# USB-Debug.net
KiCad netlist of a schematic drawn in Altium Designer
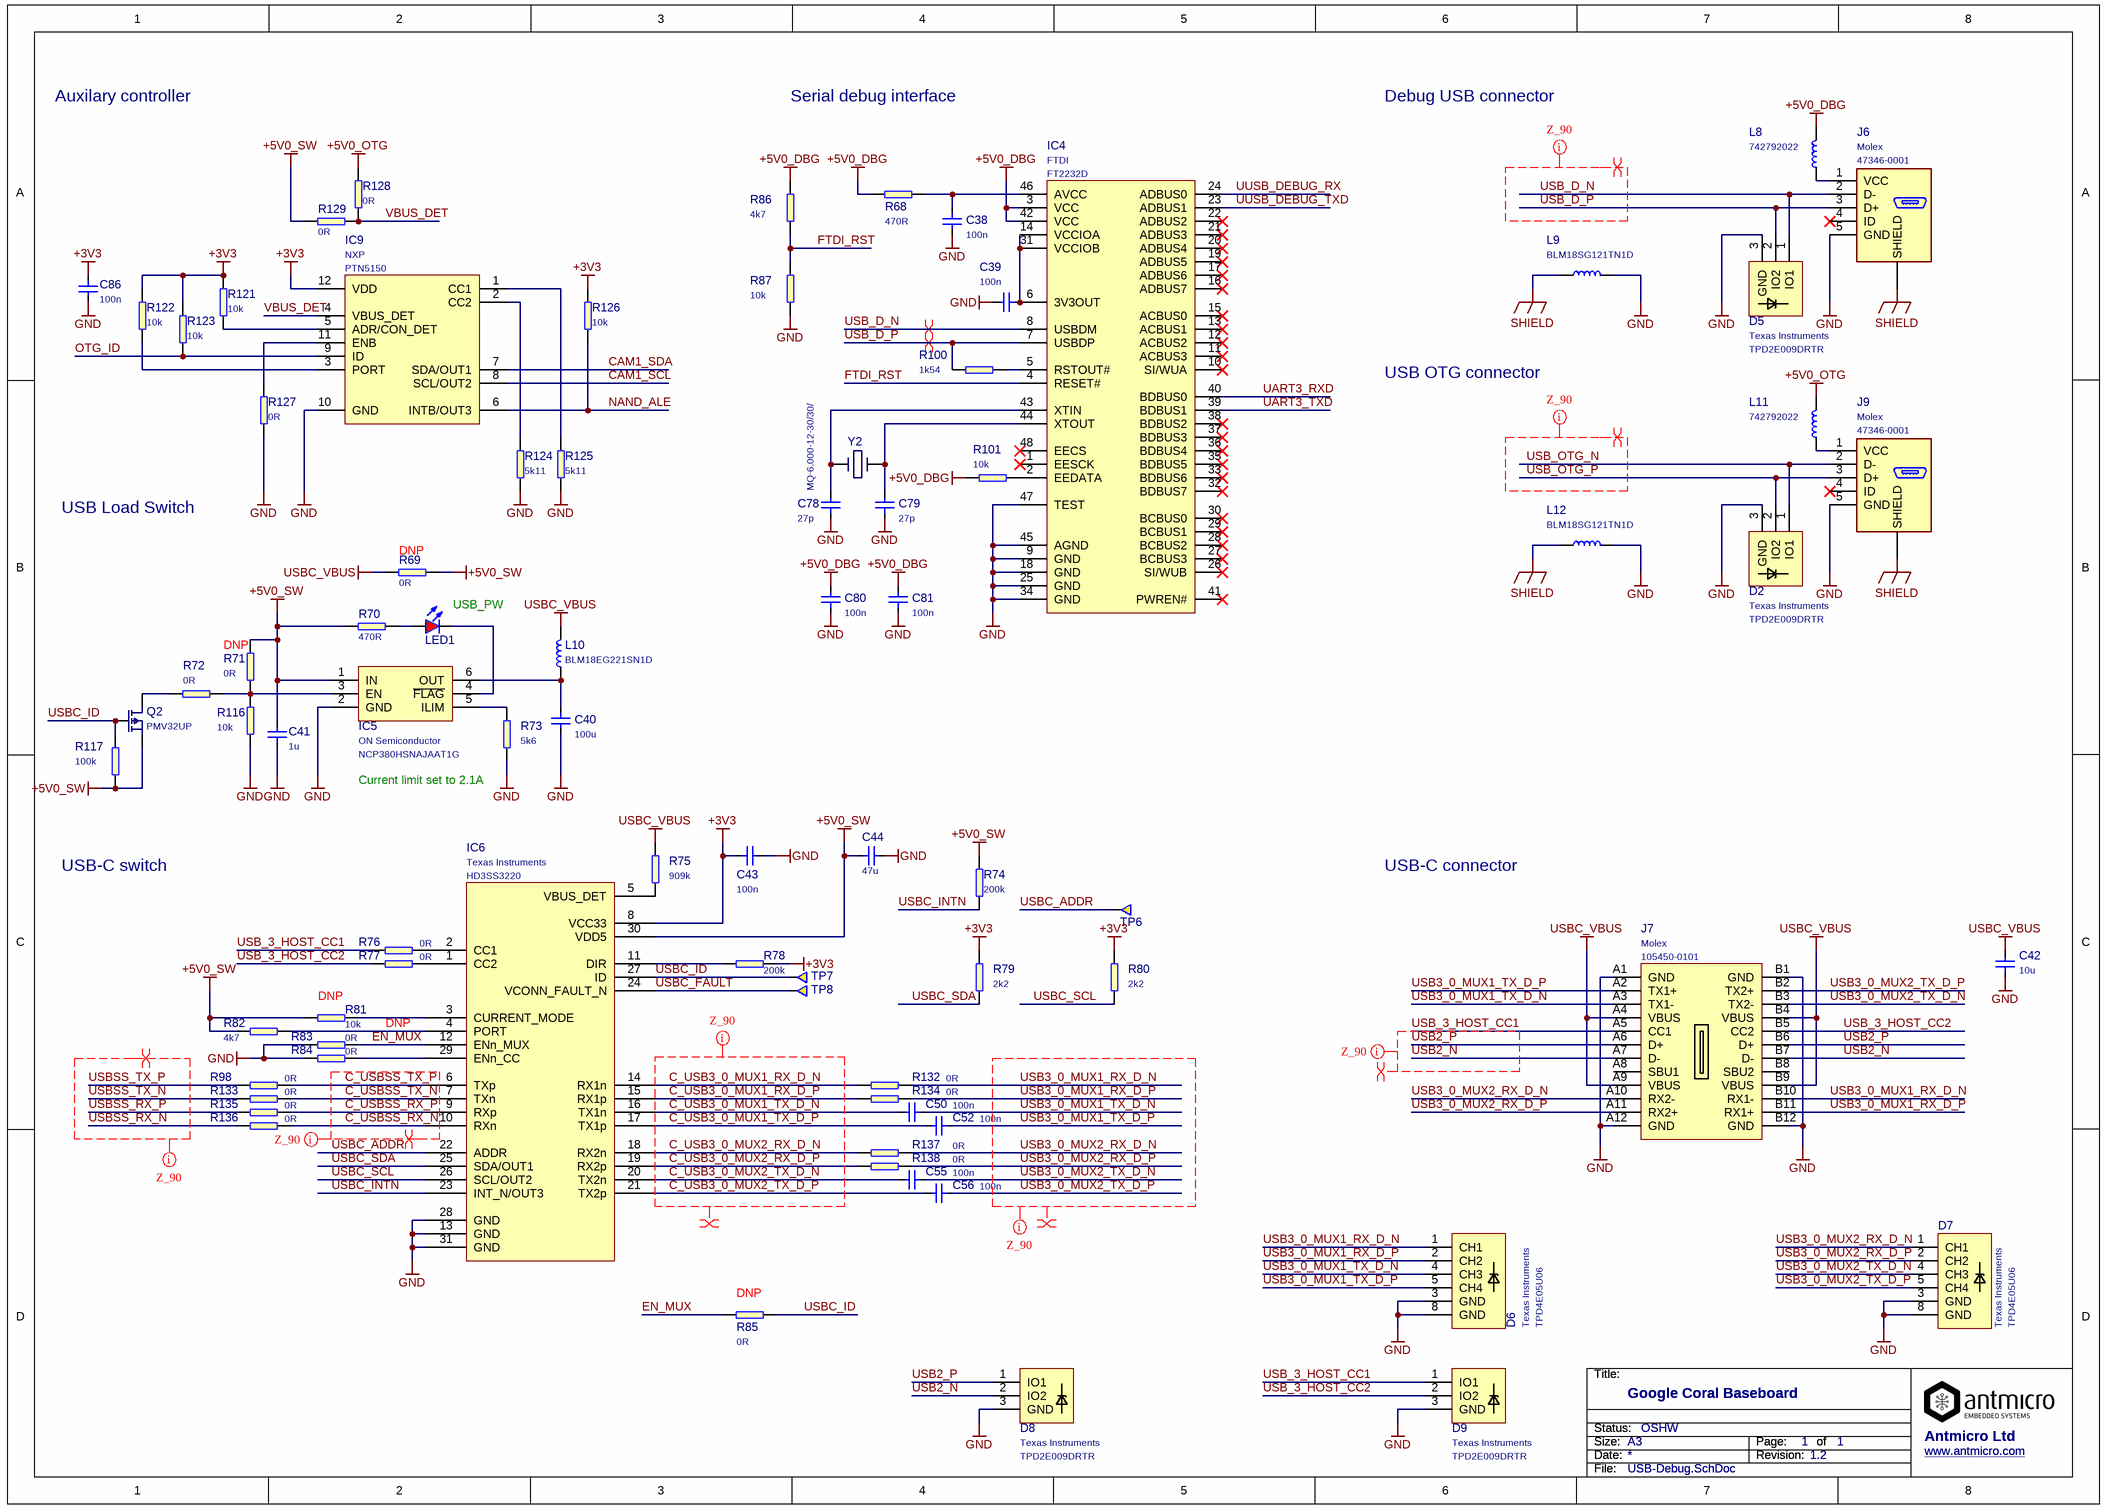
[diagram p0: USB-Debug.SchDoc]

(export (version "E")
  (design (tool "Eeschema 10.0.6"))
  (components
    (comp (ref "C38")
      (value "100n")
      (footprint "C_0402")
      (description "MLCC SMT Capacitor 100nF 0402")
      (fields (field (name "PARTNUMBER") "C_100n_0402"))
      (libsource (lib "altium-import") (part "root_3_C_"))
    )
    (comp (ref "C39")
      (value "100n")
      (footprint "C_0402")
      (description "MLCC SMT Capacitor 100nF 0402")
      (fields (field (name "PARTNUMBER") "C_100n_0402"))
      (libsource (lib "altium-import") (part "root_2_C_"))
    )
    (comp (ref "C40")
      (value "100u")
      (footprint "1210")
      (description "MLCC SMT Capacitor 100uF 1210 X5R")
      (fields (field (name "PARTNUMBER") "C_100u_1210_X5R"))
      (libsource (lib "altium-import") (part "root_3_C_"))
    )
    (comp (ref "C41")
      (value "1u")
      (footprint "0603")
      (description "MLCC SMT Capacitor 1uF 0603")
      (fields (field (name "PARTNUMBER") "C_1u_0603"))
      (libsource (lib "altium-import") (part "root_1_C_"))
    )
    (comp (ref "C42")
      (value "10u")
      (footprint "0603")
      (description "MLCC SMT Capacitor 10uF 0603")
      (fields (field (name "PARTNUMBER") "C_10u_0603"))
      (libsource (lib "altium-import") (part "root_1_C_"))
    )
    (comp (ref "C43")
      (value "100n")
      (footprint "0603")
      (description "MLCC SMT Capacitor 100nF 0603")
      (fields (field (name "PARTNUMBER") "C_100n_0603") (field (name "MANUFACTURER") "AVX"))
      (libsource (lib "altium-import") (part "root_0_C_"))
    )
    (comp (ref "C44")
      (value "47u")
      (footprint "0805")
      (description "MLCC SMT Capacitor 47uF 0805")
      (fields (field (name "PARTNUMBER") "C_47u_0805") (field (name "MANUFACTURER") "KEMET"))
      (libsource (lib "altium-import") (part "root_0_C_"))
    )
    (comp (ref "C50")
      (value "100n")
      (footprint "C_0402")
      (description "MLCC SMT Capacitor 100nF 0402")
      (fields (field (name "PARTNUMBER") "C_100n_0402"))
      (libsource (lib "altium-import") (part "root_2_C_"))
    )
    (comp (ref "C52")
      (value "100n")
      (footprint "C_0402")
      (description "MLCC SMT Capacitor 100nF 0402")
      (fields (field (name "PARTNUMBER") "C_100n_0402"))
      (libsource (lib "altium-import") (part "root_2_C_"))
    )
    (comp (ref "C55")
      (value "100n")
      (footprint "C_0402")
      (description "MLCC SMT Capacitor 100nF 0402")
      (fields (field (name "PARTNUMBER") "C_100n_0402"))
      (libsource (lib "altium-import") (part "root_2_C_"))
    )
    (comp (ref "C56")
      (value "100n")
      (footprint "C_0402")
      (description "MLCC SMT Capacitor 100nF 0402")
      (fields (field (name "PARTNUMBER") "C_100n_0402"))
      (libsource (lib "altium-import") (part "root_2_C_"))
    )
    (comp (ref "C78")
      (value "27p")
      (footprint "C_0402")
      (description "MLCC SMT Capacitor 27pF 0402")
      (fields (field (name "PARTNUMBER") "C_27p_0402"))
      (libsource (lib "altium-import") (part "root_1_C_"))
    )
    (comp (ref "C79")
      (value "27p")
      (footprint "C_0402")
      (description "MLCC SMT Capacitor 27pF 0402")
      (fields (field (name "PARTNUMBER") "C_27p_0402"))
      (libsource (lib "altium-import") (part "root_1_C_"))
    )
    (comp (ref "C80")
      (value "100n")
      (footprint "C_0402")
      (description "MLCC SMT Capacitor 100nF 0402")
      (fields (field (name "PARTNUMBER") "C_100n_0402"))
      (libsource (lib "altium-import") (part "root_1_C_"))
    )
    (comp (ref "C81")
      (value "100n")
      (footprint "C_0402")
      (description "MLCC SMT Capacitor 100nF 0402")
      (fields (field (name "PARTNUMBER") "C_100n_0402"))
      (libsource (lib "altium-import") (part "root_1_C_"))
    )
    (comp (ref "C86")
      (value "100n")
      (footprint "C_0402")
      (description "MLCC SMT Capacitor 100nF 0402")
      (fields (field (name "PARTNUMBER") "C_100n_0402"))
      (libsource (lib "altium-import") (part "root_3_C_"))
    )
    (comp (ref "D2")
      (value "TPD2E009DRTR")
      (footprint "SOT-3")
      (description "ESD Suppressors 2-CH")
      (fields (field (name "MANUFACTURER") "Texas Instruments"))
      (libsource (lib "altium-import") (part "root_3_TPD2E009_"))
    )
    (comp (ref "D5")
      (value "TPD2E009DRTR")
      (footprint "SOT-3")
      (description "ESD Suppressors 2-CH")
      (fields (field (name "MANUFACTURER") "Texas Instruments"))
      (libsource (lib "altium-import") (part "root_3_TPD2E009_"))
    )
    (comp (ref "D6")
      (value "TPD4E05U06")
      (footprint "TPD4E05U06_PASS")
      (description "ESD Suppressors 4-CH")
      (fields (field (name "PARTNUMBER") "TPD4E05U06") (field (name "MANUFACTURER") "Texas Instruments"))
      (libsource (lib "altium-import") (part "root_0_TPD4E05U06_"))
    )
    (comp (ref "D7")
      (value "TPD4E05U06")
      (footprint "TPD4E05U06_PASS")
      (description "ESD Suppressors 4-CH")
      (fields (field (name "PARTNUMBER") "TPD4E05U06") (field (name "MANUFACTURER") "Texas Instruments"))
      (libsource (lib "altium-import") (part "root_0_TPD4E05U06_"))
    )
    (comp (ref "D8")
      (value "TPD2E009DRTR")
      (footprint "SOT-3")
      (description "ESD Suppressors 2-CH")
      (fields (field (name "MANUFACTURER") "Texas Instruments"))
      (libsource (lib "altium-import") (part "root_0_TPD2E009_"))
    )
    (comp (ref "D9")
      (value "TPD2E009DRTR")
      (footprint "SOT-3")
      (description "ESD Suppressors 2-CH")
      (fields (field (name "MANUFACTURER") "Texas Instruments"))
      (libsource (lib "altium-import") (part "root_0_TPD2E009_"))
    )
    (comp (ref "IC4")
      (value "FT2232D")
      (footprint "LQFP-48")
      (description "Dual USB-UART/FIFO")
      (fields (field (name "MANUFACTURER") "FTDI"))
      (libsource (lib "altium-import") (part "root_0_FT2232_"))
    )
    (comp (ref "IC5")
      (value "NCP380HSNAJAAT1G")
      (footprint "TSOP-6")
      (description "POWER LOAD SWITCH, HIGH SIDE")
      (fields (field (name "MANUFACTURER") "ON Semiconductor"))
      (libsource (lib "altium-import") (part "root_0_NCP380HSNAJAAT1G_"))
    )
    (comp (ref "IC6")
      (value "HD3SS3220")
      (footprint "RNH0030A")
      (description "IC DRP PORT CTLR USB-C 30WQFN")
      (fields (field (name "MANUFACTURER") "Texas Instruments"))
      (libsource (lib "altium-import") (part "root_0_HD3SS3220_"))
    )
    (comp (ref "IC9")
      (value "PTN5150")
      (footprint "PTN5150")
      (description "CC logic for USB Type-C applications")
      (fields (field (name "MANUFACTURER") "NXP"))
      (libsource (lib "altium-import") (part "root_0_PTN5150_"))
    )
    (comp (ref "J6")
      (value "47346-0001")
      (footprint "CON-Molex-047346-0001")
      (description "USB - micro B Receptacle Connector 5 Position Surface Mount, Right Angle, Horizontal")
      (fields (field (name "MANUFACTURER") "Molex"))
      (libsource (lib "altium-import") (part "root_0_Micro USB B_"))
    )
    (comp (ref "J7")
      (value "105450-0101")
      (footprint "CON-Molex-105450-0101")
      (description "USB-C connector")
      (fields (field (name "PARTNUMBER") "CON-Molex-105450-0101") (field (name "MANUFACTURER") "Molex"))
      (libsource (lib "altium-import") (part "root_0_CON-Molex-105450-0101_"))
    )
    (comp (ref "J9")
      (value "47346-0001")
      (footprint "CON-Molex-047346-0001")
      (description "USB - micro B Receptacle Connector 5 Position Surface Mount, Right Angle, Horizontal")
      (fields (field (name "PARTNUMBER") "47346-0001") (field (name "MANUFACTURER") "Molex"))
      (libsource (lib "altium-import") (part "root_0_Micro USB B_"))
    )
    (comp (ref "L8")
      (value "742792022")
      (footprint "0805")
      (description "WURTH ELEKTRONIK - 742792022 - FERRITE BEAD, 0.05OHM, 2A, 0805")
      (fields (field (name "MANUFACTURER") "WURTH ELEKTRONIK"))
      (libsource (lib "altium-import") (part "root_1_Inductor SMT_"))
    )
    (comp (ref "L9")
      (value "BLM18SG121TN1D")
      (footprint "0603")
      (description "FERRITE BEAD, 0.025OHM, 3A, 0603")
      (fields (field (name "MANUFACTURER") "MURATA") (field (name "PARTNUMBER") "BLM18EG221SN1D"))
      (libsource (lib "altium-import") (part "root_0_Inductor SMT_"))
    )
    (comp (ref "L10")
      (value "BLM18EG221SN1D")
      (footprint "0603")
      (description "MURATA 	BLM18EG221SN1D  FERRITE BEAD, 0.05OHM, 2A, 0603")
      (fields (field (name "MANUFACTURER") "MURATA"))
      (libsource (lib "altium-import") (part "root_1_Inductor SMT_"))
    )
    (comp (ref "L11")
      (value "742792022")
      (footprint "0805")
      (description "WURTH ELEKTRONIK - 742792022 - FERRITE BEAD, 0.05OHM, 2A, 0805")
      (fields (field (name "MANUFACTURER") "WURTH ELEKTRONIK"))
      (libsource (lib "altium-import") (part "root_1_Inductor SMT_"))
    )
    (comp (ref "L12")
      (value "BLM18SG121TN1D")
      (footprint "0603")
      (description "FERRITE BEAD, 0.025OHM, 3A, 0603")
      (fields (field (name "MANUFACTURER") "MURATA"))
      (libsource (lib "altium-import") (part "root_0_Inductor SMT_"))
    )
    (comp (ref "LED1")
      (value "KPT-1608EC")
      (footprint "LED0603")
      (description "LED Red 0603 case")
      (fields (field (name "MANUFACTURER") "KINGBRIGHT"))
      (libsource (lib "altium-import") (part "root_0_LED_"))
    )
    (comp (ref "Q2")
      (value "PMV32UP")
      (footprint "SOT-23")
      (description "P CH, 20V, 4A")
      (fields (field (name "MANUFACTURER") "NXP"))
      (libsource (lib "altium-import") (part "root_2_mirrored_PMOS_"))
    )
    (comp (ref "R68")
      (value "470R")
      (footprint "0402")
      (description "SMT Resistor 470R 0402")
      (fields (field (name "PARTNUMBER") "R_470R_0402"))
      (libsource (lib "altium-import") (part "root_0_R_"))
    )
    (comp (ref "R69")
      (value "0R")
      (footprint "0603")
      (description "SMT Resistor 0R 0603")
      (fields (field (name "PARTNUMBER") "R_0R_0603"))
      (libsource (lib "altium-import") (part "root_0_R_"))
    )
    (comp (ref "R70")
      (value "470R")
      (footprint "0603")
      (description "SMT Resistor 470R 0603")
      (fields (field (name "PARTNUMBER") "R_470R_0603"))
      (libsource (lib "altium-import") (part "root_2_R_"))
    )
    (comp (ref "R71")
      (value "0R")
      (footprint "0402")
      (description "SMT Resistor 0402")
      (fields (field (name "PARTNUMBER") "R_0R_0402"))
      (libsource (lib "altium-import") (part "root_1_R_"))
    )
    (comp (ref "R72")
      (value "0R")
      (footprint "0402")
      (description "SMT Resistor 0402")
      (fields (field (name "PARTNUMBER") "R_0R_0402"))
      (libsource (lib "altium-import") (part "root_0_R_"))
    )
    (comp (ref "R73")
      (value "5k6")
      (footprint "0603")
      (description "SMT Resistor 5k6 0603")
      (fields (field (name "PARTNUMBER") "R_5k6_0603"))
      (libsource (lib "altium-import") (part "root_1_R_"))
    )
    (comp (ref "R74")
      (value "200k")
      (footprint "0402")
      (description "SMT Resistor 200k 0402")
      (fields (field (name "PARTNUMBER") "R_200k_0402"))
      (libsource (lib "altium-import") (part "root_1_R_"))
    )
    (comp (ref "R75")
      (value "909k")
      (footprint "0402")
      (description "SMT Resistor 9k31 0402")
      (fields (field (name "PARTNUMBER") "R_909k_0402"))
      (libsource (lib "altium-import") (part "root_1_R_"))
    )
    (comp (ref "R76")
      (value "0R")
      (footprint "0402")
      (description "SMT Resistor 0402")
      (fields (field (name "PARTNUMBER") "R_0R_0402"))
      (libsource (lib "altium-import") (part "root_0_R_"))
    )
    (comp (ref "R77")
      (value "0R")
      (footprint "0402")
      (description "SMT Resistor 0402")
      (fields (field (name "PARTNUMBER") "R_0R_0402"))
      (libsource (lib "altium-import") (part "root_0_R_"))
    )
    (comp (ref "R78")
      (value "200k")
      (footprint "0402")
      (description "SMT Resistor 200k 0402")
      (fields (field (name "PARTNUMBER") "R_200k_0402"))
      (libsource (lib "altium-import") (part "root_0_R_"))
    )
    (comp (ref "R79")
      (value "2k2")
      (footprint "0402")
      (description "RES, 2k2, 0402, 5%")
      (fields (field (name "PARTNUMBER") "R_2k2_0402"))
      (libsource (lib "altium-import") (part "root_1_R_"))
    )
    (comp (ref "R80")
      (value "2k2")
      (footprint "0402")
      (description "RES, 2k2, 0402, 5%")
      (fields (field (name "PARTNUMBER") "R_2k2_0402"))
      (libsource (lib "altium-import") (part "root_1_R_"))
    )
    (comp (ref "R81")
      (value "10k")
      (footprint "0402")
      (description "SMT Resistor 0402")
      (fields (field (name "PARTNUMBER") "R_10k_0402"))
      (libsource (lib "altium-import") (part "root_0_R_"))
    )
    (comp (ref "R82")
      (value "4k7")
      (footprint "0402")
      (description "SMT Resistor 4k7 0402")
      (fields (field (name "PARTNUMBER") "R_4k7_0402"))
      (libsource (lib "altium-import") (part "root_0_R_"))
    )
    (comp (ref "R83")
      (value "0R")
      (footprint "0402")
      (description "SMT Resistor 0402")
      (fields (field (name "PARTNUMBER") "R_0R_0402"))
      (libsource (lib "altium-import") (part "root_0_R_"))
    )
    (comp (ref "R84")
      (value "0R")
      (footprint "0402")
      (description "SMT Resistor 0402")
      (fields (field (name "PARTNUMBER") "R_0R_0402"))
      (libsource (lib "altium-import") (part "root_0_R_"))
    )
    (comp (ref "R85")
      (value "0R")
      (footprint "0402")
      (description "SMT Resistor 0402")
      (fields (field (name "PARTNUMBER") "R_0R_0402"))
      (libsource (lib "altium-import") (part "root_0_R_"))
    )
    (comp (ref "R86")
      (value "4k7")
      (footprint "0402")
      (description "SMT Resistor 4k7 0402")
      (fields (field (name "PARTNUMBER") "R_4k7_0402"))
      (libsource (lib "altium-import") (part "root_1_R_"))
    )
    (comp (ref "R87")
      (value "10k")
      (footprint "0402")
      (description "SMT Resistor 0402")
      (fields (field (name "PARTNUMBER") "R_10k_0402"))
      (libsource (lib "altium-import") (part "root_1_R_"))
    )
    (comp (ref "R98")
      (value "0R")
      (footprint "0402")
      (description "SMT Resistor 0402")
      (fields (field (name "PARTNUMBER") "R_0R_0402"))
      (libsource (lib "altium-import") (part "root_0_R_"))
    )
    (comp (ref "R100")
      (value "1k54")
      (footprint "0402")
      (description "SMT Resistor 1k54 0402")
      (fields (field (name "PARTNUMBER") "R_1k54_0402"))
      (libsource (lib "altium-import") (part "root_0_R_"))
    )
    (comp (ref "R101")
      (value "10k")
      (footprint "0402")
      (description "SMT Resistor 0402")
      (fields (field (name "PARTNUMBER") "R_10k_0402"))
      (libsource (lib "altium-import") (part "root_0_R_"))
    )
    (comp (ref "R116")
      (value "10k")
      (footprint "0402")
      (description "SMT Resistor 0402")
      (fields (field (name "PARTNUMBER") "R_10k_0402"))
      (libsource (lib "altium-import") (part "root_1_R_"))
    )
    (comp (ref "R117")
      (value "100k")
      (footprint "0402")
      (description "SMT Resistor 100k 0402")
      (fields (field (name "PARTNUMBER") "R_100k_0402"))
      (libsource (lib "altium-import") (part "root_1_R_"))
    )
    (comp (ref "R121")
      (value "10k")
      (footprint "0402")
      (description "SMT Resistor 0402")
      (fields (field (name "PARTNUMBER") "R_10k_0402"))
      (libsource (lib "altium-import") (part "root_1_R_"))
    )
    (comp (ref "R122")
      (value "10k")
      (footprint "0402")
      (description "SMT Resistor 0402")
      (fields (field (name "PARTNUMBER") "R_10k_0402"))
      (libsource (lib "altium-import") (part "root_1_R_"))
    )
    (comp (ref "R123")
      (value "10k")
      (footprint "0402")
      (description "SMT Resistor 0402")
      (fields (field (name "PARTNUMBER") "R_10k_0402"))
      (libsource (lib "altium-import") (part "root_1_R_"))
    )
    (comp (ref "R124")
      (value "5k11")
      (footprint "0402")
      (description "SMT Resistor 5k11 0402")
      (fields (field (name "PARTNUMBER") "R_5k11_0402"))
      (libsource (lib "altium-import") (part "root_1_R_"))
    )
    (comp (ref "R125")
      (value "5k11")
      (footprint "0402")
      (description "SMT Resistor 5k11 0402")
      (fields (field (name "PARTNUMBER") "R_5k11_0402"))
      (libsource (lib "altium-import") (part "root_1_R_"))
    )
    (comp (ref "R126")
      (value "10k")
      (footprint "0402")
      (description "SMT Resistor 0402")
      (fields (field (name "PARTNUMBER") "R_10k_0402"))
      (libsource (lib "altium-import") (part "root_1_R_"))
    )
    (comp (ref "R127")
      (value "0R")
      (footprint "0402")
      (description "SMT Resistor 0402")
      (fields (field (name "PARTNUMBER") "R_0R_0402"))
      (libsource (lib "altium-import") (part "root_1_R_"))
    )
    (comp (ref "R128")
      (value "0R")
      (footprint "0402")
      (description "SMT Resistor 0402")
      (fields (field (name "PARTNUMBER") "R_0R_0402"))
      (libsource (lib "altium-import") (part "root_1_R_"))
    )
    (comp (ref "R129")
      (value "0R")
      (footprint "0402")
      (description "SMT Resistor 0402")
      (fields (field (name "PARTNUMBER") "R_0R_0402"))
      (libsource (lib "altium-import") (part "root_2_R_"))
    )
    (comp (ref "R132")
      (value "0R")
      (footprint "0402")
      (description "SMT Resistor 0402")
      (fields (field (name "PARTNUMBER") "R_0R_0402"))
      (libsource (lib "altium-import") (part "root_0_R_"))
    )
    (comp (ref "R133")
      (value "0R")
      (footprint "0402")
      (description "SMT Resistor 0402")
      (fields (field (name "PARTNUMBER") "R_0R_0402"))
      (libsource (lib "altium-import") (part "root_0_R_"))
    )
    (comp (ref "R134")
      (value "0R")
      (footprint "0402")
      (description "SMT Resistor 0402")
      (fields (field (name "PARTNUMBER") "R_0R_0402"))
      (libsource (lib "altium-import") (part "root_0_R_"))
    )
    (comp (ref "R135")
      (value "0R")
      (footprint "0402")
      (description "SMT Resistor 0402")
      (fields (field (name "PARTNUMBER") "R_0R_0402"))
      (libsource (lib "altium-import") (part "root_0_R_"))
    )
    (comp (ref "R136")
      (value "0R")
      (footprint "0402")
      (description "SMT Resistor 0402")
      (fields (field (name "PARTNUMBER") "R_0R_0402"))
      (libsource (lib "altium-import") (part "root_0_R_"))
    )
    (comp (ref "R137")
      (value "0R")
      (footprint "0402")
      (description "SMT Resistor 0402")
      (fields (field (name "PARTNUMBER") "R_0R_0402"))
      (libsource (lib "altium-import") (part "root_0_R_"))
    )
    (comp (ref "R138")
      (value "0R")
      (footprint "0402")
      (description "SMT Resistor 0402")
      (fields (field (name "PARTNUMBER") "R_0R_0402"))
      (libsource (lib "altium-import") (part "root_0_R_"))
    )
    (comp (ref "TP6")
      (value "Testpad")
      (footprint "TP-R-1.5")
      (description "Testpad, round, 1.5mm")
      (libsource (lib "altium-import") (part "root_3_Testpad_"))
    )
    (comp (ref "TP7")
      (value "Testpad")
      (footprint "TP-R-1.5")
      (description "Testpad, round, 1.5mm")
      (libsource (lib "altium-import") (part "root_3_Testpad_"))
    )
    (comp (ref "TP8")
      (value "Testpad")
      (footprint "TP-R-1.5")
      (description "Testpad, round, 1.5mm")
      (libsource (lib "altium-import") (part "root_3_Testpad_"))
    )
    (comp (ref "Y2")
      (value "MQ-6.000-12-30/30/")
      (footprint "Crystal_5x7mm")
      (description "CRYSTAL, 6MHZ, 12PF, SMD,30ppm")
      (fields
        (field (name "PARTNUMBER") "CRYSTAL_6_MHz_SMD")
        (field (name "MANUFACTURER") "MERCURY UNITED ELECTRONICS")
      )
      (libsource (lib "altium-import") (part "root_0_CRYSTAL_6Mhz_"))
    )
  )
  (nets
    (net (code "1") (name "+3V3") (class "Default")
      (node (ref "C43") (pin "1") (pinfunction "1_1") (pintype "passive"))
      (node (ref "C86") (pin "1") (pinfunction "1_1") (pintype "passive"))
      (node (ref "IC6") (pin "8") (pinfunction "VCC33_8") (pintype "passive"))
      (node (ref "IC9") (pin "12") (pinfunction "VDD_12") (pintype "passive"))
      (node (ref "R121") (pin "2") (pintype "passive"))
      (node (ref "R122") (pin "2") (pintype "passive"))
      (node (ref "R123") (pin "2") (pintype "passive"))
      (node (ref "R126") (pin "2") (pintype "passive"))
      (node (ref "R78") (pin "2") (pintype "passive"))
      (node (ref "R79") (pin "2") (pintype "passive"))
      (node (ref "R80") (pin "2") (pintype "passive"))
    )
    (net (code "2") (name "+5V0_DBG") (class "Default")
      (node (ref "C80") (pin "2") (pinfunction "2_2") (pintype "passive"))
      (node (ref "C81") (pin "2") (pinfunction "2_2") (pintype "passive"))
      (node (ref "IC4") (pin "3") (pinfunction "VCC_3") (pintype "passive"))
      (node (ref "IC4") (pin "42") (pinfunction "VCC_42") (pintype "passive"))
      (node (ref "L8") (pin "2") (pintype "passive"))
      (node (ref "R101") (pin "1") (pintype "passive"))
      (node (ref "R68") (pin "1") (pintype "passive"))
      (node (ref "R86") (pin "2") (pintype "passive"))
    )
    (net (code "3") (name "+5V0_OTG") (class "Default")
      (node (ref "L11") (pin "2") (pintype "passive"))
      (node (ref "R128") (pin "2") (pintype "passive"))
    )
    (net (code "4") (name "+5V0_SW") (class "Default")
      (node (ref "C41") (pin "2") (pinfunction "2_2") (pintype "passive"))
      (node (ref "C44") (pin "1") (pinfunction "1_1") (pintype "passive"))
      (node (ref "IC5") (pin "1") (pinfunction "IN_1") (pintype "passive"))
      (node (ref "IC6") (pin "30") (pinfunction "VDD5_30") (pintype "passive"))
      (node (ref "Q2") (pin "2") (pinfunction "S_2") (pintype "passive"))
      (node (ref "R117") (pin "1") (pintype "passive"))
      (node (ref "R129") (pin "2") (pintype "passive"))
      (node (ref "R69") (pin "2") (pintype "passive"))
      (node (ref "R70") (pin "2") (pintype "passive"))
      (node (ref "R71") (pin "2") (pintype "passive"))
      (node (ref "R74") (pin "2") (pintype "passive"))
      (node (ref "R81") (pin "1") (pintype "passive"))
      (node (ref "R82") (pin "1") (pintype "passive"))
    )
    (net (code "5") (name "/CAM1_SCL") (class "Default")
      (node (ref "IC9") (pin "8") (pinfunction "SCL/OUT2_8") (pintype "passive"))
    )
    (net (code "6") (name "/CAM1_SDA") (class "Default")
      (node (ref "IC9") (pin "7") (pinfunction "SDA/OUT1_7") (pintype "passive"))
    )
    (net (code "7") (name "/C_USB3_0_MUX1_RX_D_N") (class "Default")
      (node (ref "IC6") (pin "14") (pinfunction "RX1n_14") (pintype "passive"))
      (node (ref "R132") (pin "1") (pintype "passive"))
    )
    (net (code "8") (name "/C_USB3_0_MUX1_RX_D_P") (class "Default")
      (node (ref "IC6") (pin "15") (pinfunction "RX1p_15") (pintype "passive"))
      (node (ref "R134") (pin "1") (pintype "passive"))
    )
    (net (code "9") (name "/C_USB3_0_MUX1_TX_D_N") (class "Default")
      (node (ref "C50") (pin "2") (pinfunction "2_2") (pintype "passive"))
      (node (ref "IC6") (pin "16") (pinfunction "TX1n_16") (pintype "passive"))
    )
    (net (code "10") (name "/C_USB3_0_MUX1_TX_D_P") (class "Default")
      (node (ref "C52") (pin "2") (pinfunction "2_2") (pintype "passive"))
      (node (ref "IC6") (pin "17") (pinfunction "TX1p_17") (pintype "passive"))
    )
    (net (code "11") (name "/C_USB3_0_MUX2_RX_D_N") (class "Default")
      (node (ref "IC6") (pin "18") (pinfunction "RX2n_18") (pintype "passive"))
      (node (ref "R137") (pin "1") (pintype "passive"))
    )
    (net (code "12") (name "/C_USB3_0_MUX2_RX_D_P") (class "Default")
      (node (ref "IC6") (pin "19") (pinfunction "RX2p_19") (pintype "passive"))
      (node (ref "R138") (pin "1") (pintype "passive"))
    )
    (net (code "13") (name "/C_USB3_0_MUX2_TX_D_N") (class "Default")
      (node (ref "C55") (pin "2") (pinfunction "2_2") (pintype "passive"))
      (node (ref "IC6") (pin "20") (pinfunction "TX2n_20") (pintype "passive"))
    )
    (net (code "14") (name "/C_USB3_0_MUX2_TX_D_P") (class "Default")
      (node (ref "C56") (pin "2") (pinfunction "2_2") (pintype "passive"))
      (node (ref "IC6") (pin "21") (pinfunction "TX2p_21") (pintype "passive"))
    )
    (net (code "15") (name "/C_USBSS_RX_N") (class "Default")
      (node (ref "IC6") (pin "10") (pinfunction "RXn_10") (pintype "passive"))
      (node (ref "R136") (pin "2") (pintype "passive"))
    )
    (net (code "16") (name "/C_USBSS_RX_P") (class "Default")
      (node (ref "IC6") (pin "9") (pinfunction "RXp_9") (pintype "passive"))
      (node (ref "R135") (pin "2") (pintype "passive"))
    )
    (net (code "17") (name "/C_USBSS_TX_N") (class "Default")
      (node (ref "IC6") (pin "7") (pinfunction "TXn_7") (pintype "passive"))
      (node (ref "R133") (pin "2") (pintype "passive"))
    )
    (net (code "18") (name "/C_USBSS_TX_P") (class "Default")
      (node (ref "IC6") (pin "6") (pinfunction "TXp_6") (pintype "passive"))
      (node (ref "R98") (pin "2") (pintype "passive"))
    )
    (net (code "19") (name "/EN_MUX") (class "Default")
      (node (ref "IC6") (pin "12") (pinfunction "ENn_MUX_12") (pintype "passive"))
      (node (ref "R83") (pin "2") (pintype "passive"))
      (node (ref "R85") (pin "1") (pintype "passive"))
    )
    (net (code "20") (name "/FTDI_RST") (class "Default")
      (node (ref "IC4") (pin "4") (pinfunction "RESET#_4") (pintype "passive"))
      (node (ref "R86") (pin "1") (pintype "passive"))
      (node (ref "R87") (pin "2") (pintype "passive"))
    )
    (net (code "21") (name "/NAND_ALE") (class "Default")
      (node (ref "IC9") (pin "6") (pinfunction "INTB/OUT3_6") (pintype "passive"))
      (node (ref "R126") (pin "1") (pintype "passive"))
    )
    (net (code "22") (name "/OTG_ID") (class "Default")
      (node (ref "IC9") (pin "9") (pinfunction "ID_9") (pintype "passive"))
      (node (ref "R123") (pin "1") (pintype "passive"))
    )
    (net (code "23") (name "/UART3_RXD") (class "Default")
      (node (ref "IC4") (pin "40") (pinfunction "BDBUS0_40") (pintype "passive"))
    )
    (net (code "24") (name "/UART3_TXD") (class "Default")
      (node (ref "IC4") (pin "39") (pinfunction "BDBUS1_39") (pintype "passive"))
    )
    (net (code "25") (name "/USB2_N") (class "Default")
      (node (ref "D8") (pin "2") (pinfunction "IO2_2") (pintype "passive"))
      (node (ref "J7") (pin "A7") (pinfunction "D-_A7") (pintype "passive"))
      (node (ref "J7") (pin "B7") (pinfunction "D-_B7") (pintype "passive"))
    )
    (net (code "26") (name "/USB2_P") (class "Default")
      (node (ref "D8") (pin "1") (pinfunction "IO1_1") (pintype "passive"))
      (node (ref "J7") (pin "A6") (pinfunction "D+_A6") (pintype "passive"))
      (node (ref "J7") (pin "B6") (pinfunction "D+_B6") (pintype "passive"))
    )
    (net (code "27") (name "/USB3_0_MUX1_RX_D_N") (class "Default")
      (node (ref "D6") (pin "1") (pinfunction "CH1_1") (pintype "passive"))
      (node (ref "J7") (pin "B10") (pinfunction "RX1-_B10") (pintype "passive"))
      (node (ref "R132") (pin "2") (pintype "passive"))
    )
    (net (code "28") (name "/USB3_0_MUX1_RX_D_P") (class "Default")
      (node (ref "D6") (pin "2") (pinfunction "CH2_2") (pintype "passive"))
      (node (ref "J7") (pin "B11") (pinfunction "RX1+_B11") (pintype "passive"))
      (node (ref "R134") (pin "2") (pintype "passive"))
    )
    (net (code "29") (name "/USB3_0_MUX1_TX_D_N") (class "Default")
      (node (ref "C50") (pin "1") (pinfunction "1_1") (pintype "passive"))
      (node (ref "D6") (pin "4") (pinfunction "CH3_4") (pintype "passive"))
      (node (ref "J7") (pin "A3") (pinfunction "TX1-_A3") (pintype "passive"))
    )
    (net (code "30") (name "/USB3_0_MUX1_TX_D_P") (class "Default")
      (node (ref "C52") (pin "1") (pinfunction "1_1") (pintype "passive"))
      (node (ref "D6") (pin "5") (pinfunction "CH4_5") (pintype "passive"))
      (node (ref "J7") (pin "A2") (pinfunction "TX1+_A2") (pintype "passive"))
    )
    (net (code "31") (name "/USB3_0_MUX2_RX_D_N") (class "Default")
      (node (ref "D7") (pin "1") (pinfunction "CH1_1") (pintype "passive"))
      (node (ref "J7") (pin "A10") (pinfunction "RX2-_A10") (pintype "passive"))
      (node (ref "R137") (pin "2") (pintype "passive"))
    )
    (net (code "32") (name "/USB3_0_MUX2_RX_D_P") (class "Default")
      (node (ref "D7") (pin "2") (pinfunction "CH2_2") (pintype "passive"))
      (node (ref "J7") (pin "A11") (pinfunction "RX2+_A11") (pintype "passive"))
      (node (ref "R138") (pin "2") (pintype "passive"))
    )
    (net (code "33") (name "/USB3_0_MUX2_TX_D_N") (class "Default")
      (node (ref "C55") (pin "1") (pinfunction "1_1") (pintype "passive"))
      (node (ref "D7") (pin "4") (pinfunction "CH3_4") (pintype "passive"))
      (node (ref "J7") (pin "B3") (pinfunction "TX2-_B3") (pintype "passive"))
    )
    (net (code "34") (name "/USB3_0_MUX2_TX_D_P") (class "Default")
      (node (ref "C56") (pin "1") (pinfunction "1_1") (pintype "passive"))
      (node (ref "D7") (pin "5") (pinfunction "CH4_5") (pintype "passive"))
      (node (ref "J7") (pin "B2") (pinfunction "TX2+_B2") (pintype "passive"))
    )
    (net (code "35") (name "/USBC_ADDR") (class "Default")
      (node (ref "IC6") (pin "22") (pinfunction "ADDR_22") (pintype "passive"))
      (node (ref "TP6") (pin "1") (pintype "passive"))
    )
    (net (code "36") (name "/USBC_FAULT") (class "Default")
      (node (ref "IC6") (pin "24") (pinfunction "VCONN_FAULT_N_24") (pintype "passive"))
      (node (ref "TP8") (pin "1") (pintype "passive"))
    )
    (net (code "37") (name "/USBC_ID") (class "Default")
      (node (ref "IC6") (pin "27") (pinfunction "ID_27") (pintype "passive"))
      (node (ref "Q2") (pin "1") (pinfunction "G_1") (pintype "passive"))
      (node (ref "R117") (pin "2") (pintype "passive"))
      (node (ref "R85") (pin "2") (pintype "passive"))
      (node (ref "TP7") (pin "1") (pintype "passive"))
    )
    (net (code "38") (name "/USBC_INTN") (class "Default")
      (node (ref "IC6") (pin "23") (pinfunction "INT_N/OUT3_23") (pintype "passive"))
      (node (ref "R74") (pin "1") (pintype "passive"))
    )
    (net (code "39") (name "/USBC_SCL") (class "Default")
      (node (ref "IC6") (pin "26") (pinfunction "SCL/OUT2_26") (pintype "passive"))
      (node (ref "R80") (pin "1") (pintype "passive"))
    )
    (net (code "40") (name "/USBC_SDA") (class "Default")
      (node (ref "IC6") (pin "25") (pinfunction "SDA/OUT1_25") (pintype "passive"))
      (node (ref "R79") (pin "1") (pintype "passive"))
    )
    (net (code "41") (name "/USBSS_RX_N") (class "Default") (node (ref "R136") (pin "1") (pintype "passive")))
    (net (code "42") (name "/USBSS_RX_P") (class "Default") (node (ref "R135") (pin "1") (pintype "passive")))
    (net (code "43") (name "/USBSS_TX_N") (class "Default") (node (ref "R133") (pin "1") (pintype "passive")))
    (net (code "44") (name "/USBSS_TX_P") (class "Default") (node (ref "R98") (pin "1") (pintype "passive")))
    (net (code "45") (name "/USB_3_HOST_CC1") (class "Default")
      (node (ref "D9") (pin "1") (pinfunction "IO1_1") (pintype "passive"))
      (node (ref "J7") (pin "A5") (pinfunction "CC1_A5") (pintype "passive"))
      (node (ref "R76") (pin "1") (pintype "passive"))
    )
    (net (code "46") (name "/USB_3_HOST_CC2") (class "Default")
      (node (ref "D9") (pin "2") (pinfunction "IO2_2") (pintype "passive"))
      (node (ref "J7") (pin "B5") (pinfunction "CC2_B5") (pintype "passive"))
      (node (ref "R77") (pin "1") (pintype "passive"))
    )
    (net (code "47") (name "/USB_D_N") (class "Default")
      (node (ref "D5") (pin "1") (pinfunction "IO1_1") (pintype "passive"))
      (node (ref "IC4") (pin "8") (pinfunction "USBDM_8") (pintype "passive"))
      (node (ref "J6") (pin "2") (pinfunction "D-_2") (pintype "passive"))
    )
    (net (code "48") (name "/USB_D_P") (class "Default")
      (node (ref "D5") (pin "2") (pinfunction "IO2_2") (pintype "passive"))
      (node (ref "IC4") (pin "7") (pinfunction "USBDP_7") (pintype "passive"))
      (node (ref "J6") (pin "3") (pinfunction "D+_3") (pintype "passive"))
      (node (ref "R100") (pin "1") (pintype "passive"))
    )
    (net (code "49") (name "/USB_OTG_N") (class "Default")
      (node (ref "D2") (pin "1") (pinfunction "IO1_1") (pintype "passive"))
      (node (ref "J9") (pin "2") (pinfunction "D-_2") (pintype "passive"))
    )
    (net (code "50") (name "/USB_OTG_P") (class "Default")
      (node (ref "D2") (pin "2") (pinfunction "IO2_2") (pintype "passive"))
      (node (ref "J9") (pin "3") (pinfunction "D+_3") (pintype "passive"))
    )
    (net (code "51") (name "/UUSB_DEBUG_RX") (class "Default")
      (node (ref "IC4") (pin "24") (pinfunction "ADBUS0_24") (pintype "passive"))
    )
    (net (code "52") (name "/UUSB_DEBUG_TXD") (class "Default")
      (node (ref "IC4") (pin "23") (pinfunction "ADBUS1_23") (pintype "passive"))
    )
    (net (code "53") (name "/VBUS_DET") (class "Default")
      (node (ref "IC9") (pin "4") (pinfunction "VBUS_DET_4") (pintype "passive"))
      (node (ref "R128") (pin "1") (pintype "passive"))
      (node (ref "R129") (pin "1") (pintype "passive"))
    )
    (net (code "54") (name "GND") (class "Default")
      (node (ref "C38") (pin "2") (pinfunction "2_2") (pintype "passive"))
      (node (ref "C39") (pin "2") (pinfunction "2_2") (pintype "passive"))
      (node (ref "C40") (pin "2") (pinfunction "2_2") (pintype "passive"))
      (node (ref "C41") (pin "1") (pinfunction "1_1") (pintype "passive"))
      (node (ref "C42") (pin "1") (pinfunction "1_1") (pintype "passive"))
      (node (ref "C43") (pin "2") (pinfunction "2_2") (pintype "passive"))
      (node (ref "C44") (pin "2") (pinfunction "2_2") (pintype "passive"))
      (node (ref "C78") (pin "1") (pinfunction "1_1") (pintype "passive"))
      (node (ref "C79") (pin "1") (pinfunction "1_1") (pintype "passive"))
      (node (ref "C80") (pin "1") (pinfunction "1_1") (pintype "passive"))
      (node (ref "C81") (pin "1") (pinfunction "1_1") (pintype "passive"))
      (node (ref "C86") (pin "2") (pinfunction "2_2") (pintype "passive"))
      (node (ref "D2") (pin "3") (pinfunction "GND_3") (pintype "passive"))
      (node (ref "D5") (pin "3") (pinfunction "GND_3") (pintype "passive"))
      (node (ref "D6") (pin "3") (pinfunction "GND_3") (pintype "passive"))
      (node (ref "D6") (pin "8") (pinfunction "GND_8") (pintype "passive"))
      (node (ref "D7") (pin "3") (pinfunction "GND_3") (pintype "passive"))
      (node (ref "D7") (pin "8") (pinfunction "GND_8") (pintype "passive"))
      (node (ref "D8") (pin "3") (pinfunction "GND_3") (pintype "passive"))
      (node (ref "D9") (pin "3") (pinfunction "GND_3") (pintype "passive"))
      (node (ref "IC4") (pin "18") (pinfunction "GND_18") (pintype "passive"))
      (node (ref "IC4") (pin "25") (pinfunction "GND_25") (pintype "passive"))
      (node (ref "IC4") (pin "34") (pinfunction "GND_34") (pintype "passive"))
      (node (ref "IC4") (pin "45") (pinfunction "AGND_45") (pintype "passive"))
      (node (ref "IC4") (pin "47") (pinfunction "TEST_47") (pintype "passive"))
      (node (ref "IC4") (pin "9") (pinfunction "GND_9") (pintype "passive"))
      (node (ref "IC5") (pin "2") (pinfunction "GND_2") (pintype "passive"))
      (node (ref "IC6") (pin "13") (pinfunction "GND_13") (pintype "passive"))
      (node (ref "IC6") (pin "28") (pinfunction "GND_28") (pintype "passive"))
      (node (ref "IC6") (pin "31") (pinfunction "GND_31") (pintype "passive"))
      (node (ref "IC9") (pin "10") (pinfunction "GND_10") (pintype "passive"))
      (node (ref "J6") (pin "5") (pinfunction "GND_5") (pintype "power_in"))
      (node (ref "J7") (pin "A1") (pinfunction "GND_A1") (pintype "passive"))
      (node (ref "J7") (pin "A12") (pinfunction "GND_A12") (pintype "passive"))
      (node (ref "J7") (pin "B1") (pinfunction "GND_B1") (pintype "passive"))
      (node (ref "J7") (pin "B12") (pinfunction "GND_B12") (pintype "passive"))
      (node (ref "J9") (pin "5") (pinfunction "GND_5") (pintype "power_in"))
      (node (ref "L12") (pin "2") (pintype "passive"))
      (node (ref "L9") (pin "2") (pintype "passive"))
      (node (ref "R116") (pin "1") (pintype "passive"))
      (node (ref "R124") (pin "1") (pintype "passive"))
      (node (ref "R125") (pin "1") (pintype "passive"))
      (node (ref "R127") (pin "1") (pintype "passive"))
      (node (ref "R73") (pin "1") (pintype "passive"))
      (node (ref "R83") (pin "1") (pintype "passive"))
      (node (ref "R84") (pin "1") (pintype "passive"))
      (node (ref "R87") (pin "1") (pintype "passive"))
    )
    (net (code "55") (name "Net-(IC4-3V3OUT)") (class "Default")
      (node (ref "C39") (pin "1") (pinfunction "1_1") (pintype "passive"))
      (node (ref "IC4") (pin "14") (pinfunction "VCCIOA_14") (pintype "passive"))
      (node (ref "IC4") (pin "31") (pinfunction "VCCIOB_31") (pintype "passive"))
      (node (ref "IC4") (pin "6") (pinfunction "3V3OUT_6") (pintype "passive"))
    )
    (net (code "56") (name "Net-(IC4-AVCC)") (class "Default")
      (node (ref "C38") (pin "1") (pinfunction "1_1") (pintype "passive"))
      (node (ref "IC4") (pin "46") (pinfunction "AVCC_46") (pintype "passive"))
      (node (ref "R68") (pin "2") (pintype "passive"))
    )
    (net (code "57") (name "Net-(IC4-EEDATA)") (class "Default")
      (node (ref "IC4") (pin "2") (pinfunction "EEDATA_2") (pintype "passive"))
      (node (ref "R101") (pin "2") (pintype "passive"))
    )
    (net (code "58") (name "Net-(IC4-RSTOUT#)") (class "Default")
      (node (ref "IC4") (pin "5") (pinfunction "RSTOUT#_5") (pintype "passive"))
      (node (ref "R100") (pin "2") (pintype "passive"))
    )
    (net (code "59") (name "Net-(IC4-XTIN)") (class "Default")
      (node (ref "C78") (pin "2") (pinfunction "2_2") (pintype "passive"))
      (node (ref "IC4") (pin "43") (pinfunction "XTIN_43") (pintype "passive"))
      (node (ref "Y2") (pin "1") (pinfunction "1_1") (pintype "passive"))
    )
    (net (code "60") (name "Net-(IC4-XTOUT)") (class "Default")
      (node (ref "C79") (pin "2") (pinfunction "2_2") (pintype "passive"))
      (node (ref "IC4") (pin "44") (pinfunction "XTOUT_44") (pintype "passive"))
      (node (ref "Y2") (pin "3") (pinfunction "3_3") (pintype "passive"))
    )
    (net (code "61") (name "Net-(IC5-EN)") (class "Default")
      (node (ref "IC5") (pin "3") (pinfunction "EN_3") (pintype "passive"))
      (node (ref "R116") (pin "2") (pintype "passive"))
      (node (ref "R71") (pin "1") (pintype "passive"))
      (node (ref "R72") (pin "2") (pintype "passive"))
    )
    (net (code "62") (name "Net-(IC5-ILIM)") (class "Default")
      (node (ref "IC5") (pin "5") (pinfunction "ILIM_5") (pintype "passive"))
      (node (ref "R73") (pin "2") (pintype "passive"))
    )
    (net (code "63") (name "Net-(IC5-OUT)") (class "Default")
      (node (ref "C40") (pin "1") (pinfunction "1_1") (pintype "passive"))
      (node (ref "IC5") (pin "6") (pinfunction "OUT_6") (pintype "passive"))
      (node (ref "L10") (pin "1") (pintype "passive"))
    )
    (net (code "64") (name "Net-(IC5-~{FLAG})") (class "Default")
      (node (ref "IC5") (pin "4") (pinfunction "~{FLAG}_4") (pintype "passive"))
      (node (ref "LED1") (pin "K") (pinfunction "K_K") (pintype "passive"))
    )
    (net (code "65") (name "Net-(IC6-CC1)") (class "Default")
      (node (ref "IC6") (pin "2") (pinfunction "CC1_2") (pintype "passive"))
      (node (ref "R76") (pin "2") (pintype "passive"))
    )
    (net (code "66") (name "Net-(IC6-CC2)") (class "Default")
      (node (ref "IC6") (pin "1") (pinfunction "CC2_1") (pintype "passive"))
      (node (ref "R77") (pin "2") (pintype "passive"))
    )
    (net (code "67") (name "Net-(IC6-CURRENT_MODE)") (class "Default")
      (node (ref "IC6") (pin "3") (pinfunction "CURRENT_MODE_3") (pintype "passive"))
      (node (ref "R81") (pin "2") (pintype "passive"))
    )
    (net (code "68") (name "Net-(IC6-DIR)") (class "Default")
      (node (ref "IC6") (pin "11") (pinfunction "DIR_11") (pintype "passive"))
      (node (ref "R78") (pin "1") (pintype "passive"))
    )
    (net (code "69") (name "Net-(IC6-ENn_CC)") (class "Default")
      (node (ref "IC6") (pin "29") (pinfunction "ENn_CC_29") (pintype "passive"))
      (node (ref "R84") (pin "2") (pintype "passive"))
    )
    (net (code "70") (name "Net-(IC6-PORT)") (class "Default")
      (node (ref "IC6") (pin "4") (pinfunction "PORT_4") (pintype "passive"))
      (node (ref "R82") (pin "2") (pintype "passive"))
    )
    (net (code "71") (name "Net-(IC6-VBUS_DET)") (class "Default")
      (node (ref "IC6") (pin "5") (pinfunction "VBUS_DET_5") (pintype "passive"))
      (node (ref "R75") (pin "1") (pintype "passive"))
    )
    (net (code "72") (name "Net-(IC9-ADR{slash}CON_DET)") (class "Default")
      (node (ref "IC9") (pin "5") (pinfunction "ADR/CON_DET_5") (pintype "passive"))
      (node (ref "R121") (pin "1") (pintype "passive"))
    )
    (net (code "73") (name "Net-(IC9-CC1)") (class "Default")
      (node (ref "IC9") (pin "1") (pinfunction "CC1_1") (pintype "passive"))
      (node (ref "R125") (pin "2") (pintype "passive"))
    )
    (net (code "74") (name "Net-(IC9-CC2)") (class "Default")
      (node (ref "IC9") (pin "2") (pinfunction "CC2_2") (pintype "passive"))
      (node (ref "R124") (pin "2") (pintype "passive"))
    )
    (net (code "75") (name "Net-(IC9-ENB)") (class "Default")
      (node (ref "IC9") (pin "11") (pinfunction "ENB_11") (pintype "passive"))
      (node (ref "R127") (pin "2") (pintype "passive"))
    )
    (net (code "76") (name "Net-(IC9-PORT)") (class "Default")
      (node (ref "IC9") (pin "3") (pinfunction "PORT_3") (pintype "passive"))
      (node (ref "R122") (pin "1") (pintype "passive"))
    )
    (net (code "77") (name "Net-(J6-VCC)") (class "Default")
      (node (ref "J6") (pin "1") (pinfunction "VCC_1") (pintype "power_in"))
      (node (ref "L8") (pin "1") (pintype "passive"))
    )
    (net (code "78") (name "Net-(J9-VCC)") (class "Default")
      (node (ref "J9") (pin "1") (pinfunction "VCC_1") (pintype "power_in"))
      (node (ref "L11") (pin "1") (pintype "passive"))
    )
    (net (code "79") (name "Net-(LED1-PadA)") (class "Default")
      (node (ref "LED1") (pin "A") (pinfunction "A_A") (pintype "passive"))
      (node (ref "R70") (pin "1") (pintype "passive"))
    )
    (net (code "80") (name "Net-(Q2-D)") (class "Default")
      (node (ref "Q2") (pin "3") (pinfunction "D_3") (pintype "passive"))
      (node (ref "R72") (pin "1") (pintype "passive"))
    )
    (net (code "81") (name "SHIELD") (class "Default")
      (node (ref "J6") (pin "S") (pinfunction "SHIELD_S") (pintype "passive"))
      (node (ref "J9") (pin "S") (pinfunction "SHIELD_S") (pintype "passive"))
      (node (ref "L12") (pin "1") (pintype "passive"))
      (node (ref "L9") (pin "1") (pintype "passive"))
    )
    (net (code "82") (name "USBC_VBUS") (class "Default")
      (node (ref "C42") (pin "2") (pinfunction "2_2") (pintype "passive"))
      (node (ref "J7") (pin "A4") (pinfunction "VBUS_A4") (pintype "passive"))
      (node (ref "J7") (pin "A9") (pinfunction "VBUS_A9") (pintype "passive"))
      (node (ref "J7") (pin "B4") (pinfunction "VBUS_B4") (pintype "passive"))
      (node (ref "J7") (pin "B9") (pinfunction "VBUS_B9") (pintype "passive"))
      (node (ref "L10") (pin "2") (pintype "passive"))
      (node (ref "R69") (pin "1") (pintype "passive"))
      (node (ref "R75") (pin "2") (pintype "passive"))
    )
    (net (code "83") (name "unconnected-(IC4-ACBUS0-Pad15)") (class "Default")
      (node (ref "IC4") (pin "15") (pinfunction "ACBUS0_15") (pintype "passive+no_connect"))
    )
    (net (code "84") (name "unconnected-(IC4-ACBUS1-Pad13)") (class "Default")
      (node (ref "IC4") (pin "13") (pinfunction "ACBUS1_13") (pintype "passive+no_connect"))
    )
    (net (code "85") (name "unconnected-(IC4-ACBUS2-Pad12)") (class "Default")
      (node (ref "IC4") (pin "12") (pinfunction "ACBUS2_12") (pintype "passive+no_connect"))
    )
    (net (code "86") (name "unconnected-(IC4-ACBUS3-Pad11)") (class "Default")
      (node (ref "IC4") (pin "11") (pinfunction "ACBUS3_11") (pintype "passive+no_connect"))
    )
    (net (code "87") (name "unconnected-(IC4-ADBUS2-Pad22)") (class "Default")
      (node (ref "IC4") (pin "22") (pinfunction "ADBUS2_22") (pintype "passive+no_connect"))
    )
    (net (code "88") (name "unconnected-(IC4-ADBUS3-Pad21)") (class "Default")
      (node (ref "IC4") (pin "21") (pinfunction "ADBUS3_21") (pintype "passive+no_connect"))
    )
    (net (code "89") (name "unconnected-(IC4-ADBUS4-Pad20)") (class "Default")
      (node (ref "IC4") (pin "20") (pinfunction "ADBUS4_20") (pintype "passive+no_connect"))
    )
    (net (code "90") (name "unconnected-(IC4-ADBUS5-Pad19)") (class "Default")
      (node (ref "IC4") (pin "19") (pinfunction "ADBUS5_19") (pintype "passive+no_connect"))
    )
    (net (code "91") (name "unconnected-(IC4-ADBUS6-Pad17)") (class "Default")
      (node (ref "IC4") (pin "17") (pinfunction "ADBUS6_17") (pintype "passive+no_connect"))
    )
    (net (code "92") (name "unconnected-(IC4-ADBUS7-Pad16)") (class "Default")
      (node (ref "IC4") (pin "16") (pinfunction "ADBUS7_16") (pintype "passive+no_connect"))
    )
    (net (code "93") (name "unconnected-(IC4-BCBUS0-Pad30)") (class "Default")
      (node (ref "IC4") (pin "30") (pinfunction "BCBUS0_30") (pintype "passive+no_connect"))
    )
    (net (code "94") (name "unconnected-(IC4-BCBUS1-Pad29)") (class "Default")
      (node (ref "IC4") (pin "29") (pinfunction "BCBUS1_29") (pintype "passive+no_connect"))
    )
    (net (code "95") (name "unconnected-(IC4-BCBUS2-Pad28)") (class "Default")
      (node (ref "IC4") (pin "28") (pinfunction "BCBUS2_28") (pintype "passive+no_connect"))
    )
    (net (code "96") (name "unconnected-(IC4-BCBUS3-Pad27)") (class "Default")
      (node (ref "IC4") (pin "27") (pinfunction "BCBUS3_27") (pintype "passive+no_connect"))
    )
    (net (code "97") (name "unconnected-(IC4-BDBUS2-Pad38)") (class "Default")
      (node (ref "IC4") (pin "38") (pinfunction "BDBUS2_38") (pintype "passive+no_connect"))
    )
    (net (code "98") (name "unconnected-(IC4-BDBUS3-Pad37)") (class "Default")
      (node (ref "IC4") (pin "37") (pinfunction "BDBUS3_37") (pintype "passive+no_connect"))
    )
    (net (code "99") (name "unconnected-(IC4-BDBUS4-Pad36)") (class "Default")
      (node (ref "IC4") (pin "36") (pinfunction "BDBUS4_36") (pintype "passive+no_connect"))
    )
    (net (code "100") (name "unconnected-(IC4-BDBUS5-Pad35)") (class "Default")
      (node (ref "IC4") (pin "35") (pinfunction "BDBUS5_35") (pintype "passive+no_connect"))
    )
    (net (code "101") (name "unconnected-(IC4-BDBUS6-Pad33)") (class "Default")
      (node (ref "IC4") (pin "33") (pinfunction "BDBUS6_33") (pintype "passive+no_connect"))
    )
    (net (code "102") (name "unconnected-(IC4-BDBUS7-Pad32)") (class "Default")
      (node (ref "IC4") (pin "32") (pinfunction "BDBUS7_32") (pintype "passive+no_connect"))
    )
    (net (code "103") (name "unconnected-(IC4-EECS-Pad48)") (class "Default")
      (node (ref "IC4") (pin "48") (pinfunction "EECS_48") (pintype "passive+no_connect"))
    )
    (net (code "104") (name "unconnected-(IC4-EESCK-Pad1)") (class "Default")
      (node (ref "IC4") (pin "1") (pinfunction "EESCK_1") (pintype "passive+no_connect"))
    )
    (net (code "105") (name "unconnected-(IC4-PWREN#-Pad41)") (class "Default")
      (node (ref "IC4") (pin "41") (pinfunction "PWREN#_41") (pintype "passive+no_connect"))
    )
    (net (code "106") (name "unconnected-(IC4-SI{slash}WUA-Pad10)") (class "Default")
      (node (ref "IC4") (pin "10") (pinfunction "SI/WUA_10") (pintype "passive+no_connect"))
    )
    (net (code "107") (name "unconnected-(IC4-SI{slash}WUB-Pad26)") (class "Default")
      (node (ref "IC4") (pin "26") (pinfunction "SI/WUB_26") (pintype "passive+no_connect"))
    )
    (net (code "108") (name "unconnected-(J6-ID-Pad4)") (class "Default")
      (node (ref "J6") (pin "4") (pinfunction "ID_4") (pintype "passive+no_connect"))
    )
    (net (code "109") (name "unconnected-(J7-SBU1-PadA8)") (class "Default")
      (node (ref "J7") (pin "A8") (pinfunction "SBU1_A8") (pintype "passive"))
    )
    (net (code "110") (name "unconnected-(J7-SBU2-PadB8)") (class "Default")
      (node (ref "J7") (pin "B8") (pinfunction "SBU2_B8") (pintype "passive"))
    )
    (net (code "111") (name "unconnected-(J9-ID-Pad4)") (class "Default")
      (node (ref "J9") (pin "4") (pinfunction "ID_4") (pintype "passive+no_connect"))
    )
  )
)
